# nsbsaint.net
KiCad netlist of a schematic drawn in EAGLE
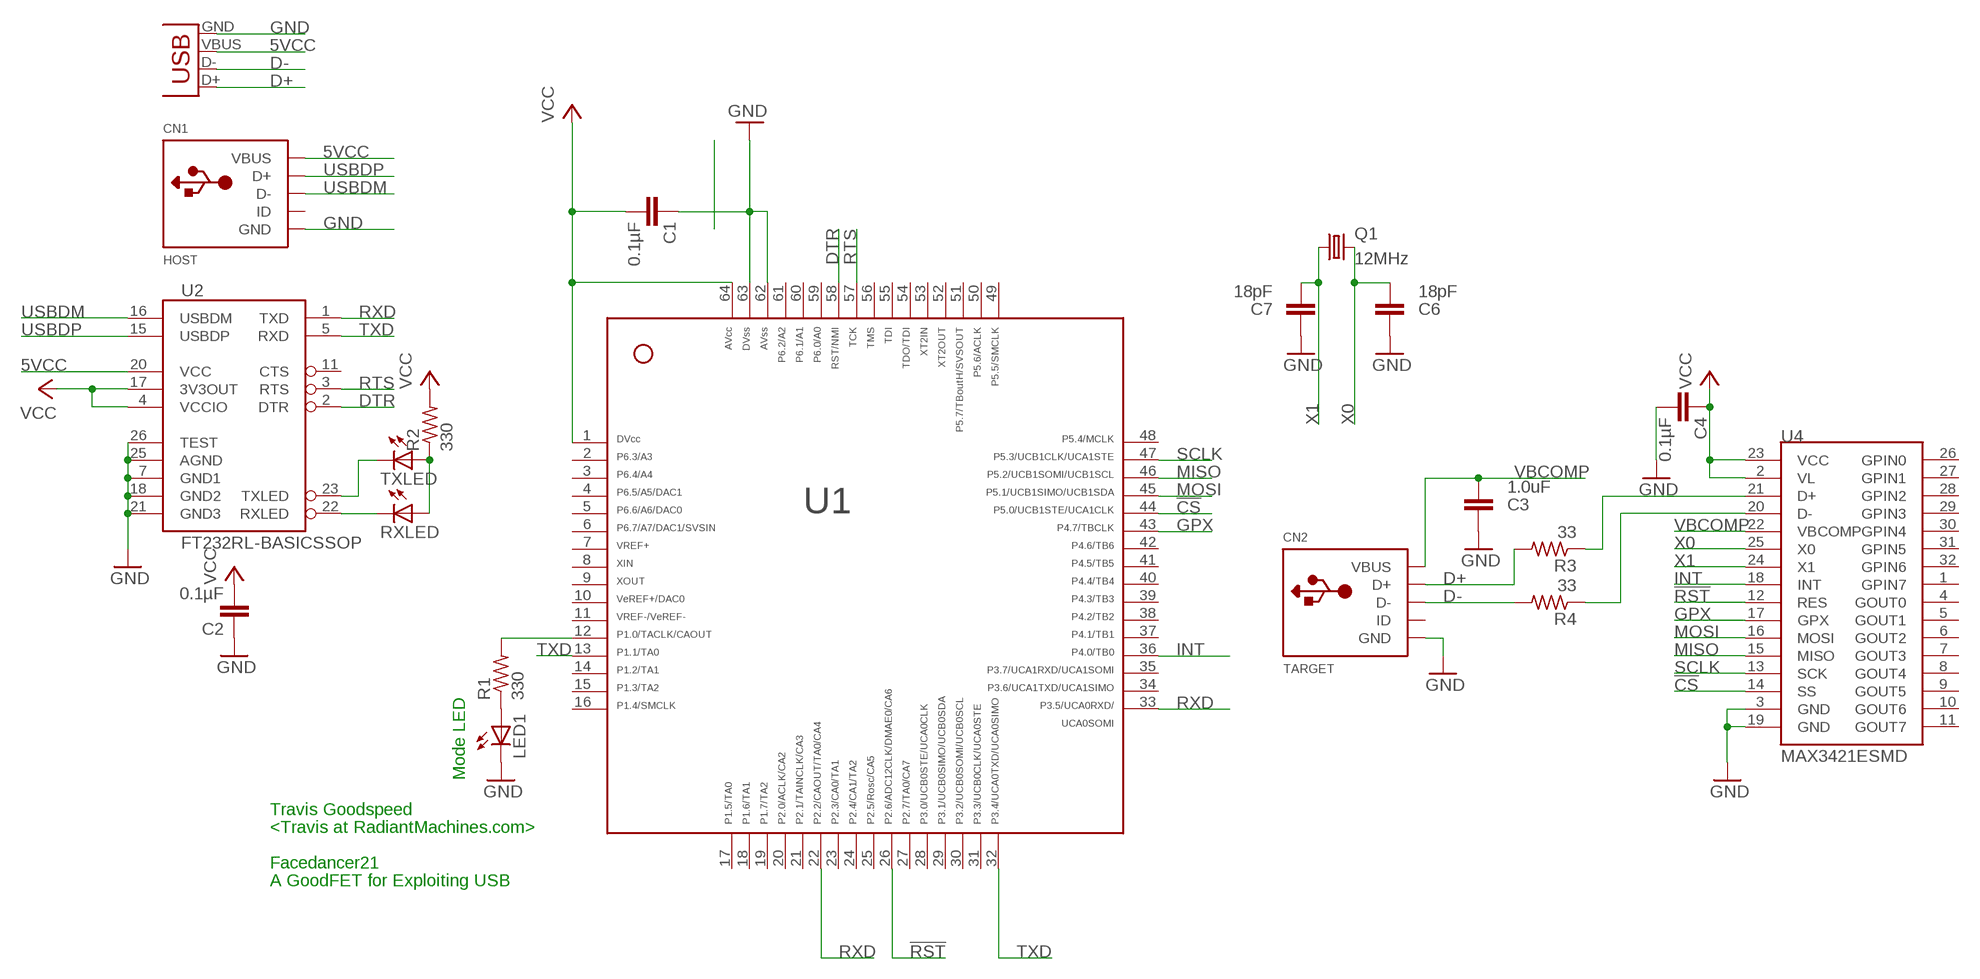
[diagram p0: schematic, sheet 1]

(export (version "E")
  (design (tool "Eeschema 10.0.6"))
  (components
    (comp (ref "C1")
      (value "0.1µF")
      (footprint "eagle-import:C0603")
      (libsource (lib "eagle-import") (part "C-EUC0603"))
    )
    (comp (ref "C2")
      (value "0.1µF")
      (footprint "eagle-import:C0603")
      (libsource (lib "eagle-import") (part "C-EUC0603"))
    )
    (comp (ref "C3")
      (value "1.0uF")
      (footprint "eagle-import:C0603")
      (libsource (lib "eagle-import") (part "C-EUC0603"))
    )
    (comp (ref "C4")
      (value "0.1µF")
      (footprint "eagle-import:C0603")
      (libsource (lib "eagle-import") (part "C-EUC0603"))
    )
    (comp (ref "C6")
      (value "18pF")
      (footprint "eagle-import:C0603")
      (libsource (lib "eagle-import") (part "C-EUC0603"))
    )
    (comp (ref "C7")
      (value "18pF")
      (footprint "eagle-import:C0603")
      (libsource (lib "eagle-import") (part "C-EUC0603"))
    )
    (comp (ref "CN1")
      (value "HOST")
      (footprint "eagle-import:USB-MINIB")
      (libsource (lib "eagle-import") (part "USBMINIB"))
    )
    (comp (ref "CN2")
      (value "TARGET")
      (footprint "eagle-import:USB-MINIB")
      (libsource (lib "eagle-import") (part "USBMINIB"))
    )
    (comp (ref "CN3")
      (value "USB-A-S")
      (footprint "eagle-import:USB-A-S")
      (libsource (lib "eagle-import") (part "USB-A-S"))
    )
    (comp (ref "LED1")
      (value "LEDCHIP-LED0603")
      (footprint "eagle-import:CHIP-LED0603")
      (libsource (lib "eagle-import") (part "LEDCHIP-LED0603"))
    )
    (comp (ref "Q1")
      (value "12MHz")
      (footprint "eagle-import:HC49UP")
      (libsource (lib "eagle-import") (part "CRYSTALHC49UP"))
    )
    (comp (ref "R1")
      (value "330")
      (footprint "eagle-import:R0603")
      (libsource (lib "eagle-import") (part "R-US_R0603"))
    )
    (comp (ref "R2")
      (value "330")
      (footprint "eagle-import:R0603")
      (libsource (lib "eagle-import") (part "R-US_R0603"))
    )
    (comp (ref "R3")
      (value "33")
      (footprint "eagle-import:R0603")
      (libsource (lib "eagle-import") (part "R-US_R0603"))
    )
    (comp (ref "R4")
      (value "33")
      (footprint "eagle-import:R0603")
      (libsource (lib "eagle-import") (part "R-US_R0603"))
    )
    (comp (ref "RXLED")
      (value "LEDCHIP-LED0603")
      (footprint "eagle-import:CHIP-LED0603")
      (libsource (lib "eagle-import") (part "LEDCHIP-LED0603"))
    )
    (comp (ref "TXLED")
      (value "LEDCHIP-LED0603")
      (footprint "eagle-import:CHIP-LED0603")
      (libsource (lib "eagle-import") (part "LEDCHIP-LED0603"))
    )
    (comp (ref "U1")
      (value "F261X---PM64")
      (footprint "eagle-import:PM_PAG64")
      (libsource (lib "eagle-import") (part "F261X---PM64"))
    )
    (comp (ref "U2")
      (value "FT232RL-BASICSSOP")
      (footprint "eagle-import:SSOP28DB")
      (libsource (lib "eagle-import") (part "FT232RL-BASICSSOP"))
    )
    (comp (ref "U4")
      (value "MAX3421ESMD")
      (footprint "eagle-import:TQFP32-5MM")
      (libsource (lib "eagle-import") (part "MAX3421ESMD"))
    )
  )
  (nets
    (net (code "1") (name "/5VCC") (class "Default")
      (node (ref "CN1") (pin "VBUS") (pinfunction "VBUS_VBUS") (pintype "power_in"))
      (node (ref "CN3") (pin "VBUS") (pinfunction "VBUS_VBUS") (pintype "bidirectional"))
      (node (ref "U2") (pin "20") (pinfunction "VCC_20") (pintype "power_in"))
    )
    (net (code "2") (name "/D+") (class "Default")
      (node (ref "CN2") (pin "D+") (pinfunction "D+_D+") (pintype "bidirectional"))
      (node (ref "CN3") (pin "D+") (pinfunction "D+_D+") (pintype "bidirectional"))
      (node (ref "R3") (pin "2") (pinfunction "2_2") (pintype "passive"))
    )
    (net (code "3") (name "/D-") (class "Default")
      (node (ref "CN2") (pin "D-") (pinfunction "D-_D-") (pintype "bidirectional"))
      (node (ref "CN3") (pin "D-") (pinfunction "D-_D-") (pintype "bidirectional"))
      (node (ref "R4") (pin "2") (pinfunction "2_2") (pintype "passive"))
    )
    (net (code "4") (name "/DTR") (class "Default")
      (node (ref "U1") (pin "58") (pinfunction "58_58") (pintype "input"))
      (node (ref "U2") (pin "2") (pinfunction "DTR_2") (pintype "bidirectional"))
    )
    (net (code "5") (name "/GPX") (class "Default")
      (node (ref "U1") (pin "43") (pinfunction "43_43") (pintype "bidirectional"))
      (node (ref "U4") (pin "17") (pinfunction "GPX_17") (pintype "bidirectional"))
    )
    (net (code "6") (name "/INT") (class "Default")
      (node (ref "U1") (pin "36") (pinfunction "36_36") (pintype "output"))
      (node (ref "U4") (pin "18") (pinfunction "INT_18") (pintype "bidirectional"))
    )
    (net (code "7") (name "/MISO") (class "Default")
      (node (ref "U1") (pin "46") (pinfunction "46_46") (pintype "bidirectional"))
      (node (ref "U4") (pin "15") (pinfunction "MISO_15") (pintype "bidirectional"))
    )
    (net (code "8") (name "/MOSI") (class "Default")
      (node (ref "U1") (pin "45") (pinfunction "45_45") (pintype "bidirectional"))
      (node (ref "U4") (pin "16") (pinfunction "MOSI_16") (pintype "bidirectional"))
    )
    (net (code "9") (name "/RTS") (class "Default")
      (node (ref "U1") (pin "57") (pinfunction "57_57") (pintype "input"))
      (node (ref "U2") (pin "3") (pinfunction "RTS_3") (pintype "bidirectional"))
    )
    (net (code "10") (name "/RXD") (class "Default")
      (node (ref "U1") (pin "22") (pinfunction "22_22") (pintype "bidirectional"))
      (node (ref "U1") (pin "33") (pinfunction "33_33") (pintype "bidirectional"))
      (node (ref "U2") (pin "1") (pinfunction "TXD_1") (pintype "output"))
    )
    (net (code "11") (name "/SCLK") (class "Default")
      (node (ref "U1") (pin "47") (pinfunction "47_47") (pintype "bidirectional"))
      (node (ref "U4") (pin "13") (pinfunction "SCK_13") (pintype "bidirectional"))
    )
    (net (code "12") (name "/TXD") (class "Default")
      (node (ref "U1") (pin "13") (pinfunction "13_13") (pintype "bidirectional"))
      (node (ref "U1") (pin "32") (pinfunction "32_32") (pintype "bidirectional"))
      (node (ref "U2") (pin "5") (pinfunction "RXD_5") (pintype "input"))
    )
    (net (code "13") (name "/USBDM") (class "Default")
      (node (ref "CN1") (pin "D-") (pinfunction "D-_D-") (pintype "bidirectional"))
      (node (ref "U2") (pin "16") (pinfunction "USBDM_16") (pintype "bidirectional"))
    )
    (net (code "14") (name "/USBDP") (class "Default")
      (node (ref "CN1") (pin "D+") (pinfunction "D+_D+") (pintype "bidirectional"))
      (node (ref "U2") (pin "15") (pinfunction "USBDP_15") (pintype "bidirectional"))
    )
    (net (code "15") (name "/VBCOMP") (class "Default")
      (node (ref "C3") (pin "2") (pinfunction "2_2") (pintype "passive"))
      (node (ref "CN2") (pin "VBUS") (pinfunction "VBUS_VBUS") (pintype "power_in"))
      (node (ref "U4") (pin "22") (pinfunction "VBCOMP_22") (pintype "bidirectional"))
    )
    (net (code "16") (name "/X0") (class "Default")
      (node (ref "C6") (pin "2") (pinfunction "2_2") (pintype "passive"))
      (node (ref "Q1") (pin "2") (pinfunction "2_2") (pintype "passive"))
      (node (ref "U4") (pin "25") (pinfunction "X0_25") (pintype "bidirectional"))
    )
    (net (code "17") (name "/X1") (class "Default")
      (node (ref "C7") (pin "2") (pinfunction "2_2") (pintype "passive"))
      (node (ref "Q1") (pin "1") (pinfunction "1_1") (pintype "passive"))
      (node (ref "U4") (pin "24") (pinfunction "X1_24") (pintype "bidirectional"))
    )
    (net (code "18") (name "/~{CS}") (class "Default")
      (node (ref "U1") (pin "44") (pinfunction "44_44") (pintype "bidirectional"))
      (node (ref "U4") (pin "14") (pinfunction "SS_14") (pintype "bidirectional"))
    )
    (net (code "19") (name "/~{RST}") (class "Default")
      (node (ref "U1") (pin "26") (pinfunction "26_26") (pintype "bidirectional"))
      (node (ref "U4") (pin "12") (pinfunction "RES_12") (pintype "bidirectional"))
    )
    (net (code "20") (name "GND") (class "Default")
      (node (ref "C1") (pin "1") (pinfunction "1_1") (pintype "passive"))
      (node (ref "C2") (pin "1") (pinfunction "1_1") (pintype "passive"))
      (node (ref "C3") (pin "1") (pinfunction "1_1") (pintype "passive"))
      (node (ref "C4") (pin "2") (pinfunction "2_2") (pintype "passive"))
      (node (ref "C6") (pin "1") (pinfunction "1_1") (pintype "passive"))
      (node (ref "C7") (pin "1") (pinfunction "1_1") (pintype "passive"))
      (node (ref "CN1") (pin "GND") (pinfunction "GND_GND") (pintype "power_in"))
      (node (ref "CN2") (pin "GND") (pinfunction "GND_GND") (pintype "power_in"))
      (node (ref "CN3") (pin "GND") (pinfunction "GND_GND") (pintype "bidirectional"))
      (node (ref "LED1") (pin "C") (pinfunction "C_C") (pintype "passive"))
      (node (ref "U1") (pin "62") (pinfunction "62_62") (pintype "power_in"))
      (node (ref "U1") (pin "63") (pinfunction "63_63") (pintype "power_in"))
      (node (ref "U2") (pin "18") (pinfunction "GND2_18") (pintype "power_in"))
      (node (ref "U2") (pin "21") (pinfunction "GND3_21") (pintype "power_in"))
      (node (ref "U2") (pin "25") (pinfunction "AGND_25") (pintype "power_in"))
      (node (ref "U2") (pin "26") (pinfunction "TEST_26") (pintype "input"))
      (node (ref "U2") (pin "7") (pinfunction "GND1_7") (pintype "power_in"))
      (node (ref "U4") (pin "19") (pinfunction "GND_19") (pintype "bidirectional"))
      (node (ref "U4") (pin "3") (pinfunction "GND_3") (pintype "bidirectional"))
    )
    (net (code "21") (name "Net-(LED1-PadA)") (class "Default")
      (node (ref "LED1") (pin "A") (pinfunction "A_A") (pintype "passive"))
      (node (ref "R1") (pin "1") (pinfunction "1_1") (pintype "passive"))
    )
    (net (code "22") (name "Net-(R1-Pad2)") (class "Default")
      (node (ref "R1") (pin "2") (pinfunction "2_2") (pintype "passive"))
      (node (ref "U1") (pin "12") (pinfunction "12_12") (pintype "bidirectional"))
    )
    (net (code "23") (name "Net-(R2-Pad1)") (class "Default")
      (node (ref "R2") (pin "1") (pinfunction "1_1") (pintype "passive"))
      (node (ref "RXLED") (pin "A") (pinfunction "A_A") (pintype "passive"))
      (node (ref "TXLED") (pin "A") (pinfunction "A_A") (pintype "passive"))
    )
    (net (code "24") (name "Net-(U2-RXLED)") (class "Default")
      (node (ref "RXLED") (pin "C") (pinfunction "C_C") (pintype "passive"))
      (node (ref "U2") (pin "22") (pinfunction "RXLED_22") (pintype "bidirectional"))
    )
    (net (code "25") (name "Net-(U2-TXLED)") (class "Default")
      (node (ref "TXLED") (pin "C") (pinfunction "C_C") (pintype "passive"))
      (node (ref "U2") (pin "23") (pinfunction "TXLED_23") (pintype "bidirectional"))
    )
    (net (code "26") (name "Net-(U4-D+)") (class "Default")
      (node (ref "R3") (pin "1") (pinfunction "1_1") (pintype "passive"))
      (node (ref "U4") (pin "21") (pinfunction "D+_21") (pintype "bidirectional"))
    )
    (net (code "27") (name "Net-(U4-D-)") (class "Default")
      (node (ref "R4") (pin "1") (pinfunction "1_1") (pintype "passive"))
      (node (ref "U4") (pin "20") (pinfunction "D-_20") (pintype "bidirectional"))
    )
    (net (code "28") (name "VCC") (class "Default")
      (node (ref "C1") (pin "2") (pinfunction "2_2") (pintype "passive"))
      (node (ref "C2") (pin "2") (pinfunction "2_2") (pintype "passive"))
      (node (ref "C4") (pin "1") (pinfunction "1_1") (pintype "passive"))
      (node (ref "R2") (pin "2") (pinfunction "2_2") (pintype "passive"))
      (node (ref "U1") (pin "1") (pinfunction "1_1") (pintype "power_in"))
      (node (ref "U1") (pin "64") (pinfunction "64_64") (pintype "power_in"))
      (node (ref "U2") (pin "17") (pinfunction "3V3OUT_17") (pintype "output"))
      (node (ref "U2") (pin "4") (pinfunction "VCCIO_4") (pintype "power_in"))
      (node (ref "U4") (pin "2") (pinfunction "VL_2") (pintype "bidirectional"))
      (node (ref "U4") (pin "23") (pinfunction "VCC_23") (pintype "bidirectional"))
    )
    (net (code "29") (name "unconnected-(CN1-PadID)") (class "Default")
      (node (ref "CN1") (pin "ID") (pinfunction "ID_ID") (pintype "bidirectional"))
    )
    (net (code "30") (name "unconnected-(CN2-PadID)") (class "Default")
      (node (ref "CN2") (pin "ID") (pinfunction "ID_ID") (pintype "bidirectional"))
    )
    (net (code "31") (name "unconnected-(U1-Pad2)") (class "Default")
      (node (ref "U1") (pin "2") (pinfunction "2_2") (pintype "bidirectional"))
    )
    (net (code "32") (name "unconnected-(U1-Pad3)") (class "Default")
      (node (ref "U1") (pin "3") (pinfunction "3_3") (pintype "bidirectional"))
    )
    (net (code "33") (name "unconnected-(U1-Pad4)") (class "Default")
      (node (ref "U1") (pin "4") (pinfunction "4_4") (pintype "bidirectional"))
    )
    (net (code "34") (name "unconnected-(U1-Pad5)") (class "Default")
      (node (ref "U1") (pin "5") (pinfunction "5_5") (pintype "bidirectional"))
    )
    (net (code "35") (name "unconnected-(U1-Pad6)") (class "Default")
      (node (ref "U1") (pin "6") (pinfunction "6_6") (pintype "bidirectional"))
    )
    (net (code "36") (name "unconnected-(U1-Pad7)") (class "Default")
      (node (ref "U1") (pin "7") (pinfunction "7_7") (pintype "output"))
    )
    (net (code "37") (name "unconnected-(U1-Pad8)") (class "Default")
      (node (ref "U1") (pin "8") (pinfunction "8_8") (pintype "input"))
    )
    (net (code "38") (name "unconnected-(U1-Pad9)") (class "Default")
      (node (ref "U1") (pin "9") (pinfunction "9_9") (pintype "output"))
    )
    (net (code "39") (name "unconnected-(U1-Pad10)") (class "Default")
      (node (ref "U1") (pin "10") (pinfunction "10_10") (pintype "bidirectional"))
    )
    (net (code "40") (name "unconnected-(U1-Pad11)") (class "Default")
      (node (ref "U1") (pin "11") (pinfunction "11_11") (pintype "bidirectional"))
    )
    (net (code "41") (name "unconnected-(U1-Pad14)") (class "Default")
      (node (ref "U1") (pin "14") (pinfunction "14_14") (pintype "bidirectional"))
    )
    (net (code "42") (name "unconnected-(U1-Pad15)") (class "Default")
      (node (ref "U1") (pin "15") (pinfunction "15_15") (pintype "bidirectional"))
    )
    (net (code "43") (name "unconnected-(U1-Pad16)") (class "Default")
      (node (ref "U1") (pin "16") (pinfunction "16_16") (pintype "bidirectional"))
    )
    (net (code "44") (name "unconnected-(U1-Pad17)") (class "Default")
      (node (ref "U1") (pin "17") (pinfunction "17_17") (pintype "bidirectional"))
    )
    (net (code "45") (name "unconnected-(U1-Pad18)") (class "Default")
      (node (ref "U1") (pin "18") (pinfunction "18_18") (pintype "bidirectional"))
    )
    (net (code "46") (name "unconnected-(U1-Pad19)") (class "Default")
      (node (ref "U1") (pin "19") (pinfunction "19_19") (pintype "bidirectional"))
    )
    (net (code "47") (name "unconnected-(U1-Pad20)") (class "Default")
      (node (ref "U1") (pin "20") (pinfunction "20_20") (pintype "bidirectional"))
    )
    (net (code "48") (name "unconnected-(U1-Pad21)") (class "Default")
      (node (ref "U1") (pin "21") (pinfunction "21_21") (pintype "bidirectional"))
    )
    (net (code "49") (name "unconnected-(U1-Pad23)") (class "Default")
      (node (ref "U1") (pin "23") (pinfunction "23_23") (pintype "bidirectional"))
    )
    (net (code "50") (name "unconnected-(U1-Pad24)") (class "Default")
      (node (ref "U1") (pin "24") (pinfunction "24_24") (pintype "bidirectional"))
    )
    (net (code "51") (name "unconnected-(U1-Pad25)") (class "Default")
      (node (ref "U1") (pin "25") (pinfunction "25_25") (pintype "bidirectional"))
    )
    (net (code "52") (name "unconnected-(U1-Pad27)") (class "Default")
      (node (ref "U1") (pin "27") (pinfunction "27_27") (pintype "bidirectional"))
    )
    (net (code "53") (name "unconnected-(U1-Pad28)") (class "Default")
      (node (ref "U1") (pin "28") (pinfunction "28_28") (pintype "bidirectional"))
    )
    (net (code "54") (name "unconnected-(U1-Pad29)") (class "Default")
      (node (ref "U1") (pin "29") (pinfunction "29_29") (pintype "bidirectional"))
    )
    (net (code "55") (name "unconnected-(U1-Pad30)") (class "Default")
      (node (ref "U1") (pin "30") (pinfunction "30_30") (pintype "bidirectional"))
    )
    (net (code "56") (name "unconnected-(U1-Pad31)") (class "Default")
      (node (ref "U1") (pin "31") (pinfunction "31_31") (pintype "bidirectional"))
    )
    (net (code "57") (name "unconnected-(U1-Pad34)") (class "Default")
      (node (ref "U1") (pin "34") (pinfunction "34_34") (pintype "bidirectional"))
    )
    (net (code "58") (name "unconnected-(U1-Pad35)") (class "Default")
      (node (ref "U1") (pin "35") (pinfunction "35_35") (pintype "bidirectional"))
    )
    (net (code "59") (name "unconnected-(U1-Pad37)") (class "Default")
      (node (ref "U1") (pin "37") (pinfunction "37_37") (pintype "bidirectional"))
    )
    (net (code "60") (name "unconnected-(U1-Pad38)") (class "Default")
      (node (ref "U1") (pin "38") (pinfunction "38_38") (pintype "bidirectional"))
    )
    (net (code "61") (name "unconnected-(U1-Pad39)") (class "Default")
      (node (ref "U1") (pin "39") (pinfunction "39_39") (pintype "bidirectional"))
    )
    (net (code "62") (name "unconnected-(U1-Pad40)") (class "Default")
      (node (ref "U1") (pin "40") (pinfunction "40_40") (pintype "input"))
    )
    (net (code "63") (name "unconnected-(U1-Pad41)") (class "Default")
      (node (ref "U1") (pin "41") (pinfunction "41_41") (pintype "bidirectional"))
    )
    (net (code "64") (name "unconnected-(U1-Pad42)") (class "Default")
      (node (ref "U1") (pin "42") (pinfunction "42_42") (pintype "bidirectional"))
    )
    (net (code "65") (name "unconnected-(U1-Pad48)") (class "Default")
      (node (ref "U1") (pin "48") (pinfunction "48_48") (pintype "bidirectional"))
    )
    (net (code "66") (name "unconnected-(U1-Pad49)") (class "Default")
      (node (ref "U1") (pin "49") (pinfunction "49_49") (pintype "bidirectional"))
    )
    (net (code "67") (name "unconnected-(U1-Pad50)") (class "Default")
      (node (ref "U1") (pin "50") (pinfunction "50_50") (pintype "bidirectional"))
    )
    (net (code "68") (name "unconnected-(U1-Pad51)") (class "Default")
      (node (ref "U1") (pin "51") (pinfunction "51_51") (pintype "bidirectional"))
    )
    (net (code "69") (name "unconnected-(U1-Pad52)") (class "Default")
      (node (ref "U1") (pin "52") (pinfunction "52_52") (pintype "output"))
    )
    (net (code "70") (name "unconnected-(U1-Pad53)") (class "Default")
      (node (ref "U1") (pin "53") (pinfunction "53_53") (pintype "input"))
    )
    (net (code "71") (name "unconnected-(U1-Pad54)") (class "Default")
      (node (ref "U1") (pin "54") (pinfunction "54_54") (pintype "bidirectional"))
    )
    (net (code "72") (name "unconnected-(U1-Pad55)") (class "Default")
      (node (ref "U1") (pin "55") (pinfunction "55_55") (pintype "input"))
    )
    (net (code "73") (name "unconnected-(U1-Pad56)") (class "Default")
      (node (ref "U1") (pin "56") (pinfunction "56_56") (pintype "input"))
    )
    (net (code "74") (name "unconnected-(U1-Pad59)") (class "Default")
      (node (ref "U1") (pin "59") (pinfunction "59_59") (pintype "bidirectional"))
    )
    (net (code "75") (name "unconnected-(U1-Pad60)") (class "Default")
      (node (ref "U1") (pin "60") (pinfunction "60_60") (pintype "bidirectional"))
    )
    (net (code "76") (name "unconnected-(U1-Pad61)") (class "Default")
      (node (ref "U1") (pin "61") (pinfunction "61_61") (pintype "bidirectional"))
    )
    (net (code "77") (name "unconnected-(U2-CTS-Pad11)") (class "Default")
      (node (ref "U2") (pin "11") (pinfunction "CTS_11") (pintype "bidirectional"))
    )
    (net (code "78") (name "unconnected-(U4-GOUT0-Pad4)") (class "Default")
      (node (ref "U4") (pin "4") (pinfunction "GOUT0_4") (pintype "bidirectional"))
    )
    (net (code "79") (name "unconnected-(U4-GOUT1-Pad5)") (class "Default")
      (node (ref "U4") (pin "5") (pinfunction "GOUT1_5") (pintype "bidirectional"))
    )
    (net (code "80") (name "unconnected-(U4-GOUT2-Pad6)") (class "Default")
      (node (ref "U4") (pin "6") (pinfunction "GOUT2_6") (pintype "bidirectional"))
    )
    (net (code "81") (name "unconnected-(U4-GOUT3-Pad7)") (class "Default")
      (node (ref "U4") (pin "7") (pinfunction "GOUT3_7") (pintype "bidirectional"))
    )
    (net (code "82") (name "unconnected-(U4-GOUT4-Pad8)") (class "Default")
      (node (ref "U4") (pin "8") (pinfunction "GOUT4_8") (pintype "bidirectional"))
    )
    (net (code "83") (name "unconnected-(U4-GOUT5-Pad9)") (class "Default")
      (node (ref "U4") (pin "9") (pinfunction "GOUT5_9") (pintype "bidirectional"))
    )
    (net (code "84") (name "unconnected-(U4-GOUT6-Pad10)") (class "Default")
      (node (ref "U4") (pin "10") (pinfunction "GOUT6_10") (pintype "bidirectional"))
    )
    (net (code "85") (name "unconnected-(U4-GOUT7-Pad11)") (class "Default")
      (node (ref "U4") (pin "11") (pinfunction "GOUT7_11") (pintype "bidirectional"))
    )
    (net (code "86") (name "unconnected-(U4-GPIN0-Pad26)") (class "Default")
      (node (ref "U4") (pin "26") (pinfunction "GPIN0_26") (pintype "bidirectional"))
    )
    (net (code "87") (name "unconnected-(U4-GPIN1-Pad27)") (class "Default")
      (node (ref "U4") (pin "27") (pinfunction "GPIN1_27") (pintype "bidirectional"))
    )
    (net (code "88") (name "unconnected-(U4-GPIN2-Pad28)") (class "Default")
      (node (ref "U4") (pin "28") (pinfunction "GPIN2_28") (pintype "bidirectional"))
    )
    (net (code "89") (name "unconnected-(U4-GPIN3-Pad29)") (class "Default")
      (node (ref "U4") (pin "29") (pinfunction "GPIN3_29") (pintype "bidirectional"))
    )
    (net (code "90") (name "unconnected-(U4-GPIN4-Pad30)") (class "Default")
      (node (ref "U4") (pin "30") (pinfunction "GPIN4_30") (pintype "bidirectional"))
    )
    (net (code "91") (name "unconnected-(U4-GPIN5-Pad31)") (class "Default")
      (node (ref "U4") (pin "31") (pinfunction "GPIN5_31") (pintype "bidirectional"))
    )
    (net (code "92") (name "unconnected-(U4-GPIN6-Pad32)") (class "Default")
      (node (ref "U4") (pin "32") (pinfunction "GPIN6_32") (pintype "bidirectional"))
    )
    (net (code "93") (name "unconnected-(U4-GPIN7-Pad1)") (class "Default")
      (node (ref "U4") (pin "1") (pinfunction "GPIN7_1") (pintype "bidirectional"))
    )
  )
)
